# Tsop_Receiver.net
KiCad netlist of a schematic drawn in EAGLE
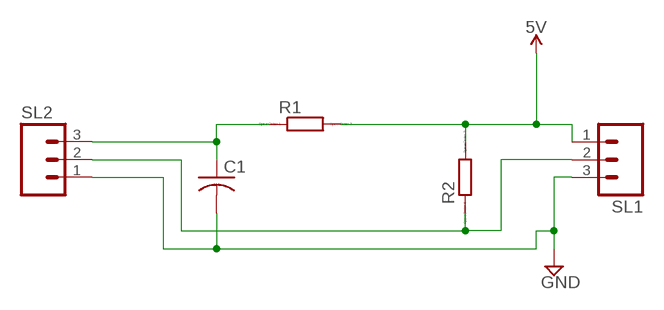
[diagram p0: schematic, sheet 1]

(export (version "E")
  (design (tool "Eeschema 10.0.6"))
  (components
    (comp (ref "C1")
      (value "C-US025-024X044")
      (footprint "eagle-import:C025-024X044")
      (libsource (lib "eagle-import") (part "C-US025-024X044"))
    )
    (comp (ref "R1")
      (value "R0207/10")
      (footprint "eagle-import:0207_10")
      (libsource (lib "eagle-import") (part "R0207/10"))
    )
    (comp (ref "R2")
      (value "R0207/10")
      (footprint "eagle-import:0207_10")
      (libsource (lib "eagle-import") (part "R0207/10"))
    )
    (comp (ref "SL1")
      (value "M03")
      (footprint "eagle-import:03P")
      (libsource (lib "eagle-import") (part "M03"))
    )
    (comp (ref "SL2")
      (value "M03")
      (footprint "eagle-import:03P")
      (libsource (lib "eagle-import") (part "M03"))
    )
  )
  (nets
    (net (code "1") (name "5V") (class "Default")
      (node (ref "R1") (pin "2") (pinfunction "2_2") (pintype "passive"))
      (node (ref "R2") (pin "2") (pinfunction "2_2") (pintype "passive"))
      (node (ref "SL1") (pin "1") (pinfunction "1_1") (pintype "passive"))
    )
    (net (code "2") (name "GND") (class "Default")
      (node (ref "C1") (pin "2") (pinfunction "2_2") (pintype "passive"))
      (node (ref "SL1") (pin "3") (pinfunction "3_3") (pintype "passive"))
      (node (ref "SL2") (pin "1") (pinfunction "1_1") (pintype "passive"))
    )
    (net (code "3") (name "Net-(C1-Pad1)") (class "Default")
      (node (ref "C1") (pin "1") (pinfunction "1_1") (pintype "passive"))
      (node (ref "R1") (pin "1") (pinfunction "1_1") (pintype "passive"))
      (node (ref "SL2") (pin "3") (pinfunction "3_3") (pintype "passive"))
    )
    (net (code "4") (name "Net-(R2-Pad1)") (class "Default")
      (node (ref "R2") (pin "1") (pinfunction "1_1") (pintype "passive"))
      (node (ref "SL1") (pin "2") (pinfunction "2_2") (pintype "passive"))
      (node (ref "SL2") (pin "2") (pinfunction "2_2") (pintype "passive"))
    )
  )
)
